# Crawler_Sensor_V2_0.net
KiCad netlist of a schematic drawn in Altium Designer
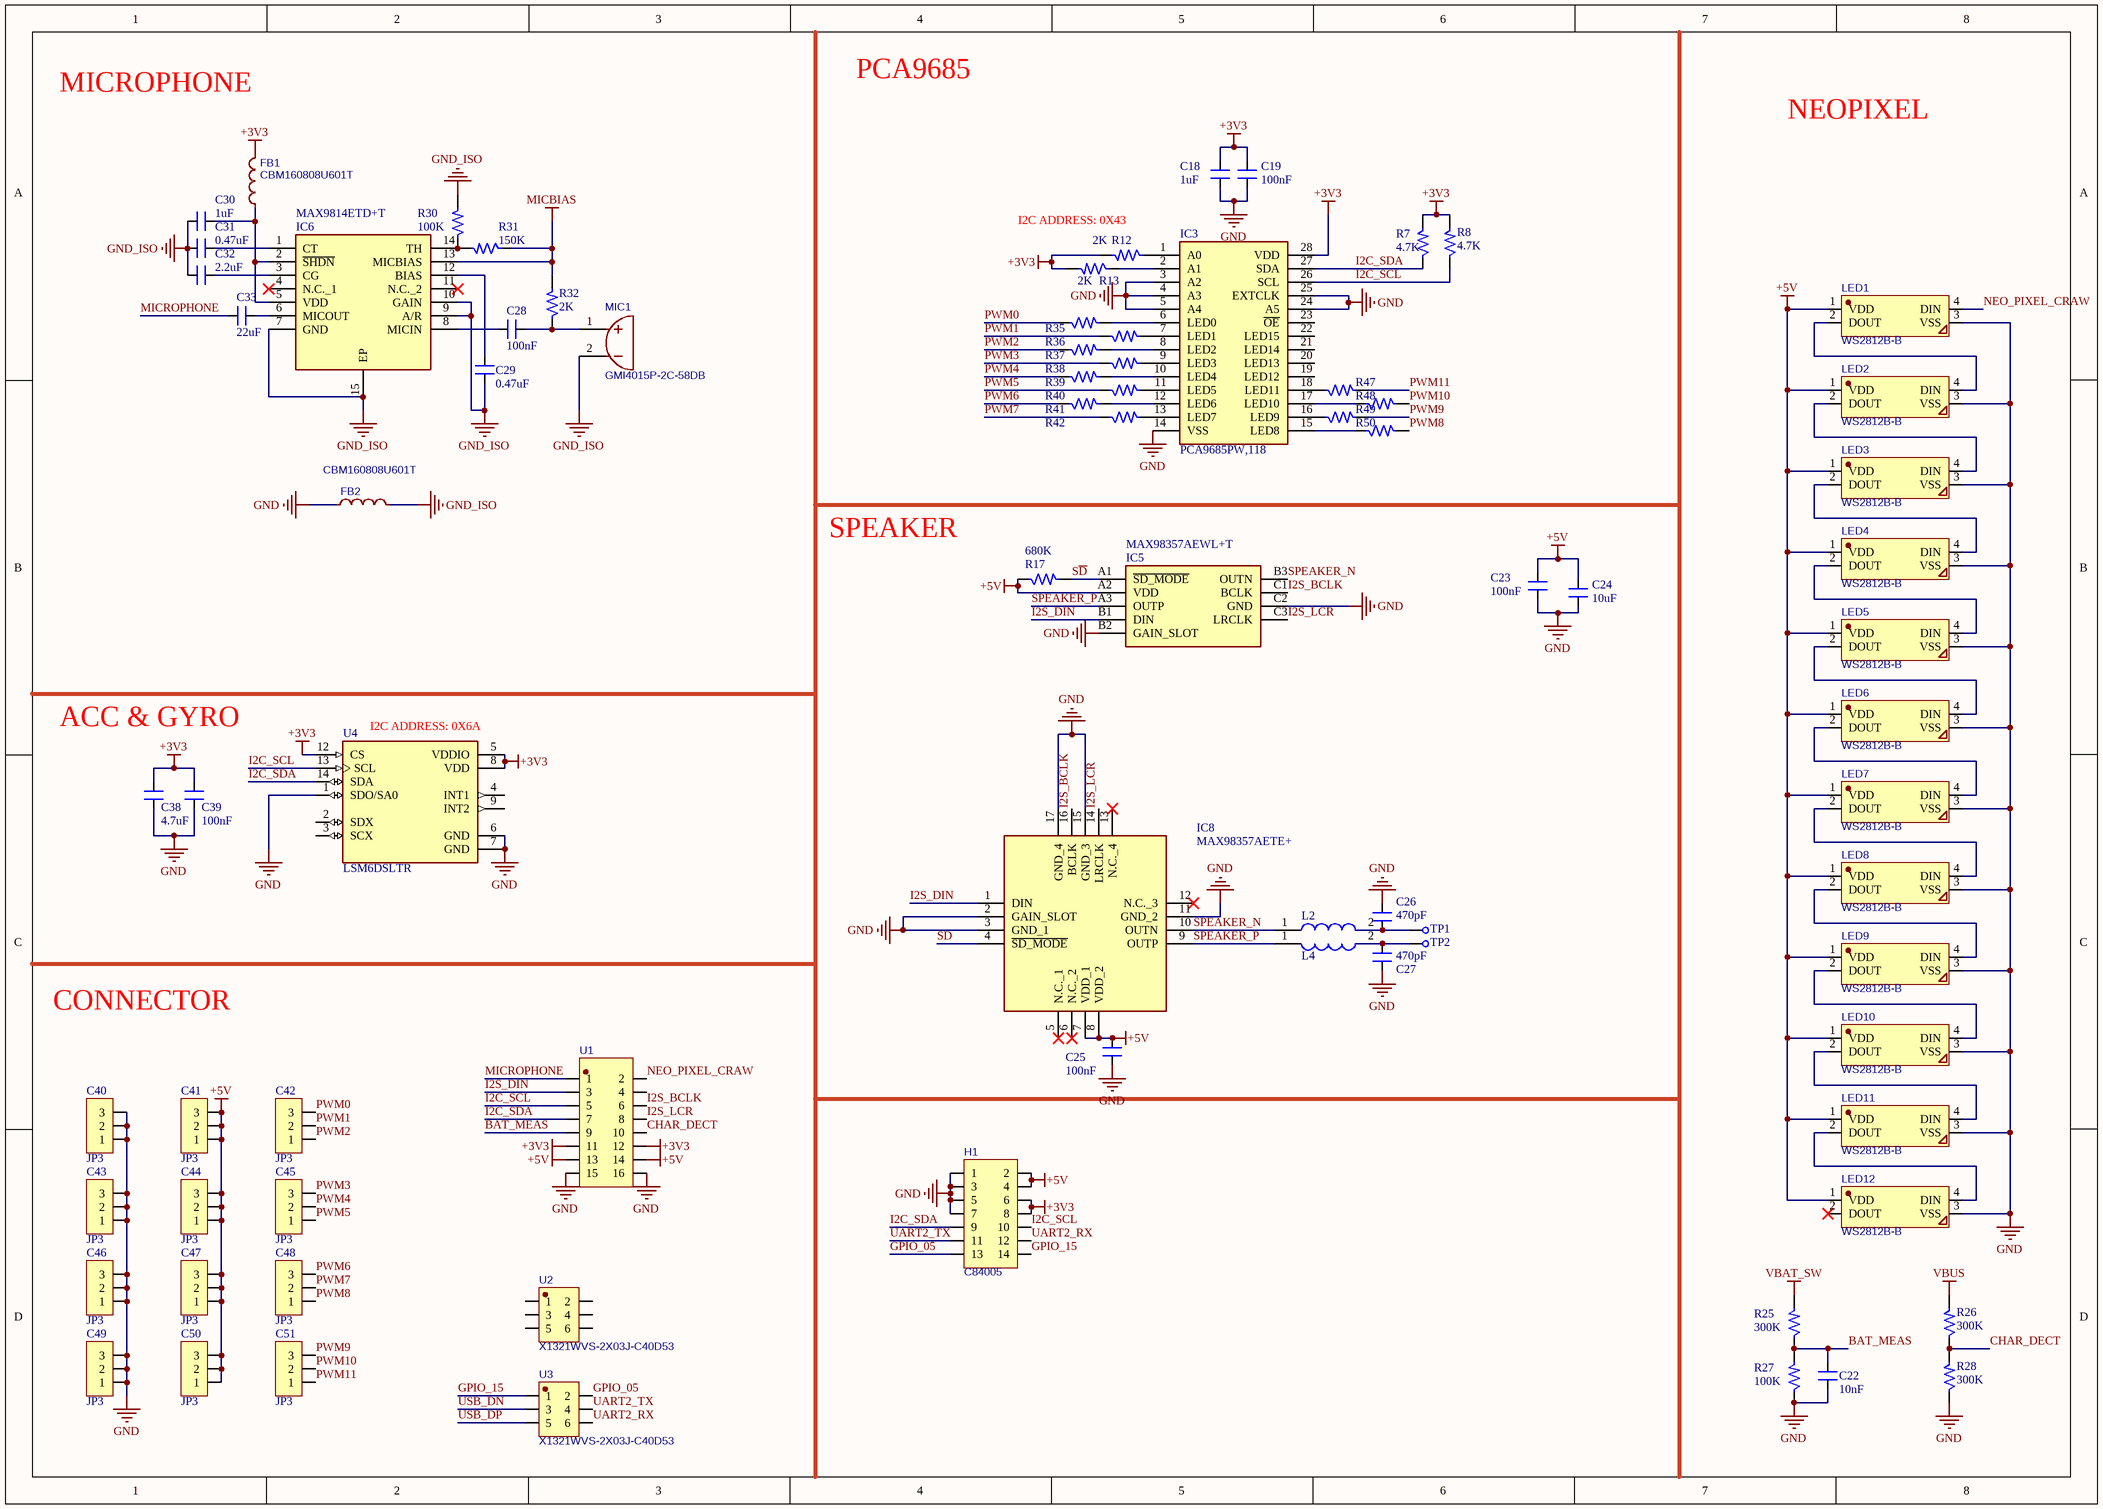
[diagram p0: Crawler_Sensor_V2.0.SchDoc]

(export (version "E")
  (design (tool "Eeschema 10.0.6"))
  (components
    (comp (ref "C18")
      (value "1uF")
      (footprint "CAP_0402")
      (description "1µF ±10% 16V Ceramic Capacitor X5R 0402 (1005 Metric)")
      (fields
        (field (name "MANUFACTURER") "Knowles Novacap")
        (field (name "MANUFACTURER PART NUMBER") "0402BW105K160YT")
      )
      (libsource (lib "EsteemPCB_SOM_Course_schlib") (part "CAP_1uF-16V-10%-0402"))
    )
    (comp (ref "C19")
      (value "100nF")
      (footprint "CAP_0402")
      (description "0.1µF ±10% 25V Ceramic Capacitor X7R 0402 (1005 Metric)")
      (fields
        (field (name "MANUFACTURER") "Walsin Technology Corporation")
        (field (name "MANUFACTURER PART NUMBER") "0402B104K250CT")
      )
      (libsource (lib "EsteemPCB_SOM_Course_schlib") (part "CAP_100nF-25V-10%-0402"))
    )
    (comp (ref "C22")
      (value "10nF")
      (footprint "CAP_0402")
      (description "10000pF ±10% 10V Ceramic Capacitor X7R 0402 (1005 Metric)")
      (fields
        (field (name "MANUFACTURER") "AVX Corporation")
        (field (name "MANUFACTURER PART NUMBER") "0402ZC103KAT2A")
      )
      (libsource (lib "EsteemPCB_SOM_Course_schlib") (part "CAP_10nF-10V-10%-0402"))
    )
    (comp (ref "C23")
      (value "100nF")
      (footprint "CAP_0402")
      (description "0.1µF ±10% 10V Ceramic Capacitor X7R 0402 (1005 Metric)")
      (fields
        (field (name "MANUFACTURER") "Yageo")
        (field (name "MANUFACTURER PART NUMBER") "CC0402KRX7R6BB104")
      )
      (libsource (lib "EsteemPCB_SOM_Course_schlib") (part "CAP_100nF-10V-10%-0402"))
    )
    (comp (ref "C24")
      (value "10uF")
      (footprint "CAP_0402")
      (description "10µF ±20% 10V Ceramic Capacitor X5R 0402 (1005 Metric)")
      (fields
        (field (name "MANUFACTURER PART NUMBER") "CL05A106MP5NUNC")
        (field (name "MANUFACTURER") "Samsung Electro-Mechanics")
      )
      (libsource (lib "EsteemPCB_SOM_Course_schlib") (part "CAP_10uF-10V-20%-0402"))
    )
    (comp (ref "C25")
      (value "100nF")
      (footprint "CAP_0402")
      (description "0.1µF ±10% 10V Ceramic Capacitor X7R 0402 (1005 Metric)")
      (fields
        (field (name "MANUFACTURER") "Yageo")
        (field (name "MANUFACTURER PART NUMBER") "CC0402KRX7R6BB104")
      )
      (libsource (lib "EsteemPCB_SOM_Course_schlib") (part "CAP_100nF-10V-10%-0402"))
    )
    (comp (ref "C26")
      (value "470pF")
      (footprint "CAP_0402")
      (description "470pF ±10% 10V Ceramic Capacitor C0G, NP0 0402 (1005 Metric)")
      (fields
        (field (name "MANUFACTURER") "KEMET")
        (field (name "MANUFACTURER PART NUMBER") "C0402C470K8GAC7867")
      )
      (libsource (lib "EsteemPCB_SOM_Course_schlib") (part "CAP_47pF-10V-10%-0402"))
    )
    (comp (ref "C27")
      (value "470pF")
      (footprint "CAP_0402")
      (description "470pF ±10% 10V Ceramic Capacitor C0G, NP0 0402 (1005 Metric)")
      (fields
        (field (name "MANUFACTURER") "KEMET")
        (field (name "MANUFACTURER PART NUMBER") "C0402C470K8GAC7867")
      )
      (libsource (lib "EsteemPCB_SOM_Course_schlib") (part "CAP_47pF-10V-10%-0402"))
    )
    (comp (ref "C28")
      (value "100nF")
      (footprint "CAP_0402")
      (description "0.1µF ±10% 10V Ceramic Capacitor X7R 0402 (1005 Metric)")
      (fields
        (field (name "MANUFACTURER") "Yageo")
        (field (name "MANUFACTURER PART NUMBER") "CC0402KRX7R6BB104")
      )
      (libsource (lib "EsteemPCB_SOM_Course_schlib") (part "CAP_100nF-10V-10%-0402"))
    )
    (comp (ref "C29")
      (value "0.47uF")
      (footprint "CAP_0402")
      (description "0.47µF ±10% 10V Ceramic Capacitor X6S 0402 (1005 Metric)")
      (fields
        (field (name "MANUFACTURER") "Murata Electronics")
        (field (name "MANUFACTURER PART NUMBER") "GRT155C81A105KE01D")
      )
      (libsource (lib "EsteemPCB_SOM_Course_schlib") (part "CAP_1uF-10V-10%-0402"))
    )
    (comp (ref "C30")
      (value "1uF")
      (footprint "CAP_0402")
      (description "1µF ±10% 10V Ceramic Capacitor X6S 0402 (1005 Metric)")
      (fields
        (field (name "MANUFACTURER") "Murata Electronics")
        (field (name "MANUFACTURER PART NUMBER") "GRT155C81A105KE01D")
      )
      (libsource (lib "EsteemPCB_SOM_Course_schlib") (part "CAP_1uF-10V-10%-0402"))
    )
    (comp (ref "C31")
      (value "0.47uF")
      (footprint "CAP_0402")
      (description "0.47µF ±10% 10V Ceramic Capacitor X6S 0402 (1005 Metric)")
      (fields
        (field (name "MANUFACTURER") "Murata Electronics")
        (field (name "MANUFACTURER PART NUMBER") "GRT155C81A105KE01D")
      )
      (libsource (lib "EsteemPCB_SOM_Course_schlib") (part "CAP_1uF-10V-10%-0402"))
    )
    (comp (ref "C32")
      (value "2.2uF")
      (footprint "CAP_0402")
      (description "2.2µF ±10% 10V Ceramic Capacitor X5R 0402 (1005 Metric)")
      (fields
        (field (name "MANUFACTURER") "Murata Electronics")
        (field (name "MANUFACTURER PART NUMBER") "GRM155R61A225KE95D")
      )
      (libsource (lib "EsteemPCB_SOM_Course_schlib") (part "CAP_2.2uF-10V-10%-0402"))
    )
    (comp (ref "C33")
      (value "22uF")
      (footprint "CAP_0603")
      (description "22µF ±20% 10V Ceramic Capacitor X5R 0603 (1608 Metric)")
      (fields
        (field (name "MANUFACTURER") "Murata Electronics")
        (field (name "MANUFACTURER PART NUMBER") "GRM188R61A226ME15D")
      )
      (libsource (lib "EsteemPCB_SOM_Course_schlib") (part "CAP_22uF-10V-20%-0603"))
    )
    (comp (ref "C38")
      (value "4.7uF")
      (footprint "CAP_0402")
      (description "4.7µF ±10% 10V Ceramic Capacitor X5R 0402 (1005 Metric)")
      (fields
        (field (name "MANUFACTURER") "Samsung Electro-Mechanics")
        (field (name "MANUFACTURER PART NUMBER") "CL05A475KP5NRNC")
      )
      (libsource (lib "EsteemPCB_SOM_Course_schlib") (part "CAP_4.7uF-10V-10%-0402"))
    )
    (comp (ref "C39")
      (value "100nF")
      (footprint "CAP_0402")
      (description "0.1µF ±10% 10V Ceramic Capacitor X7R 0402 (1005 Metric)")
      (fields
        (field (name "MANUFACTURER") "Yageo")
        (field (name "MANUFACTURER PART NUMBER") "CC0402KRX7R6BB104")
      )
      (libsource (lib "EsteemPCB_SOM_Course_schlib") (part "CAP_100nF-10V-10%-0402"))
    )
    (comp (ref "C40")
      (value "JP3")
      (footprint "JP3-D1T")
      (description "WR-PHD 2.54 mm Angled Socket Header")
      (fields
        (field (name "MANUFACTURER") "Würth Elektronik eiSos GmbH")
        (field (name "PARTNO") "613003143121")
        (field (name "CREATED BY") "Karrer Zheng")
      )
      (libsource (lib "LIBRARY") (part "JP3"))
    )
    (comp (ref "C41")
      (value "JP3")
      (footprint "JP3-D1T")
      (description "WR-PHD 2.54 mm Angled Socket Header")
      (fields
        (field (name "MANUFACTURER") "Würth Elektronik eiSos GmbH")
        (field (name "PARTNO") "613003143121")
        (field (name "CREATED BY") "Karrer Zheng")
      )
      (libsource (lib "LIBRARY") (part "JP3"))
    )
    (comp (ref "C42")
      (value "JP3")
      (footprint "JP3-D1T")
      (description "WR-PHD 2.54 mm Angled Socket Header")
      (fields
        (field (name "MANUFACTURER") "Würth Elektronik eiSos GmbH")
        (field (name "PARTNO") "613003143121")
        (field (name "CREATED BY") "Karrer Zheng")
      )
      (libsource (lib "LIBRARY") (part "JP3"))
    )
    (comp (ref "C43")
      (value "JP3")
      (footprint "JP3-D1T")
      (description "WR-PHD 2.54 mm Angled Socket Header")
      (fields
        (field (name "MANUFACTURER") "Würth Elektronik eiSos GmbH")
        (field (name "PARTNO") "613003143121")
        (field (name "CREATED BY") "Karrer Zheng")
      )
      (libsource (lib "LIBRARY") (part "JP3"))
    )
    (comp (ref "C44")
      (value "JP3")
      (footprint "JP3-D1T")
      (description "WR-PHD 2.54 mm Angled Socket Header")
      (fields
        (field (name "MANUFACTURER") "Würth Elektronik eiSos GmbH")
        (field (name "PARTNO") "613003143121")
        (field (name "CREATED BY") "Karrer Zheng")
      )
      (libsource (lib "LIBRARY") (part "JP3"))
    )
    (comp (ref "C45")
      (value "JP3")
      (footprint "JP3-D1T")
      (description "WR-PHD 2.54 mm Angled Socket Header")
      (fields
        (field (name "MANUFACTURER") "Würth Elektronik eiSos GmbH")
        (field (name "PARTNO") "613003143121")
        (field (name "CREATED BY") "Karrer Zheng")
      )
      (libsource (lib "LIBRARY") (part "JP3"))
    )
    (comp (ref "C46")
      (value "JP3")
      (footprint "JP3-D1T")
      (description "WR-PHD 2.54 mm Angled Socket Header")
      (fields
        (field (name "MANUFACTURER") "Würth Elektronik eiSos GmbH")
        (field (name "PARTNO") "613003143121")
        (field (name "CREATED BY") "Karrer Zheng")
      )
      (libsource (lib "LIBRARY") (part "JP3"))
    )
    (comp (ref "C47")
      (value "JP3")
      (footprint "JP3-D1T")
      (description "WR-PHD 2.54 mm Angled Socket Header")
      (fields
        (field (name "MANUFACTURER") "Würth Elektronik eiSos GmbH")
        (field (name "PARTNO") "613003143121")
        (field (name "CREATED BY") "Karrer Zheng")
      )
      (libsource (lib "LIBRARY") (part "JP3"))
    )
    (comp (ref "C48")
      (value "JP3")
      (footprint "JP3-D1T")
      (description "WR-PHD 2.54 mm Angled Socket Header")
      (fields
        (field (name "MANUFACTURER") "Würth Elektronik eiSos GmbH")
        (field (name "PARTNO") "613003143121")
        (field (name "CREATED BY") "Karrer Zheng")
      )
      (libsource (lib "LIBRARY") (part "JP3"))
    )
    (comp (ref "C49")
      (value "JP3")
      (footprint "JP3-D1T")
      (description "WR-PHD 2.54 mm Angled Socket Header")
      (fields
        (field (name "MANUFACTURER") "Würth Elektronik eiSos GmbH")
        (field (name "PARTNO") "613003143121")
        (field (name "CREATED BY") "Karrer Zheng")
      )
      (libsource (lib "LIBRARY") (part "JP3"))
    )
    (comp (ref "C50")
      (value "JP3")
      (footprint "JP3-D1T")
      (description "WR-PHD 2.54 mm Angled Socket Header")
      (fields
        (field (name "MANUFACTURER") "Würth Elektronik eiSos GmbH")
        (field (name "PARTNO") "613003143121")
        (field (name "CREATED BY") "Karrer Zheng")
      )
      (libsource (lib "LIBRARY") (part "JP3"))
    )
    (comp (ref "C51")
      (value "JP3")
      (footprint "JP3-D1T")
      (description "WR-PHD 2.54 mm Angled Socket Header")
      (fields
        (field (name "MANUFACTURER") "Würth Elektronik eiSos GmbH")
        (field (name "PARTNO") "613003143121")
        (field (name "CREATED BY") "Karrer Zheng")
      )
      (libsource (lib "LIBRARY") (part "JP3"))
    )
    (comp (ref "FB1")
      (value "CBM160808U601T")
      (footprint "L0603")
      (fields (field (name "BOM_SUPPLIER PART") "C394427") (field (name "CONTRIBUTOR") "LCSC"))
      (libsource (lib "") (part "CBM160808U601T_1"))
    )
    (comp (ref "FB2")
      (value "CBM160808U601T")
      (footprint "L0603")
      (fields (field (name "BOM_SUPPLIER PART") "C394427") (field (name "CONTRIBUTOR") "LCSC"))
      (libsource (lib "SamacSys") (part "CBM160808U601T"))
    )
    (comp (ref "H1")
      (value "C84005")
      (footprint "HDR-SMD_14P-P2.54-V-F-R2-C7-S2.54")
      (fields (field (name "BOM_MANUFACTURER PART") "2.54-2*7P立贴母") (field (name "CONTRIBUTOR") "LCSC"))
      (libsource (lib "SamacSys") (part "C84005"))
    )
    (comp (ref "IC3")
      (value "PCA9685PW,118")
      (footprint "SamacSys:SOP65P640X110-28N")
      (description "Integrated Circuit")
      (fields (field (name "MOUSER PART NUMBER") "771-PCA9685PW,118"))
      (libsource (lib "*") (part "PCA9685PW,118"))
    )
    (comp (ref "IC5")
      (value "MAX98357AEWL+T")
      (footprint "SamacSys:BGA9C40P3X3_144X135X69")
      (description "Integrated Circuit")
      (fields (field (name "MOUSER PART NUMBER") "700-MAX98357AEWL+T"))
      (libsource (lib "*") (part "MAX98357AEWL+T"))
    )
    (comp (ref "IC6")
      (value "MAX9814ETD+T")
      (footprint "SamacSys:SON40P300X300X80-15N")
      (description "Integrated Circuit")
      (fields (field (name "MOUSER PART NUMBER") "700-MAX9814ETDT"))
      (libsource (lib "*") (part "MAX9814ETD+T"))
    )
    (comp (ref "IC8")
      (value "MAX98357AETE+")
      (footprint "SamacSys:QFN50P300X300X80-17N")
      (description "Integrated Circuit")
      (fields (field (name "MOUSER PART NUMBER") "700-MAX98357AETE+"))
      (libsource (lib "SamacSys") (part "MAX98357AETE+"))
    )
    (comp (ref "L2")
      (value "MLF2012C680KT000")
      (footprint "INDC2012X145N")
      (description "Inductor")
      (fields (field (name "MOUSER PART NUMBER") "810-MLF2012C680KT000"))
      (libsource (lib "SamacSys") (part "MLF2012C680KT000"))
    )
    (comp (ref "L4")
      (value "MLF2012C680KT000")
      (footprint "INDC2012X145N")
      (description "Inductor")
      (fields (field (name "MOUSER PART NUMBER") "810-MLF2012C680KT000"))
      (libsource (lib "") (part "MLF2012C680KT000_1"))
    )
    (comp (ref "LED1")
      (value "WS2812B-B")
      (footprint "LED-SMD_4P-L5.0-W5.0-BL_TC5050RGB")
      (fields
        (field (name "BOM_MANUFACTURER PART") "WS2812B-B/W")
        (field (name "BOM_SUPPLIER PART") "C114586")
        (field (name "CONTRIBUTOR") "LCSC")
      )
      (libsource (lib "SamacSys") (part "WS2812B-B"))
    )
    (comp (ref "LED2")
      (value "WS2812B-B")
      (footprint "LED-SMD_4P-L5.0-W5.0-BL_TC5050RGB")
      (fields
        (field (name "BOM_MANUFACTURER PART") "WS2812B-B/W")
        (field (name "BOM_SUPPLIER PART") "C114586")
        (field (name "CONTRIBUTOR") "LCSC")
      )
      (libsource (lib "SamacSys") (part "WS2812B-B"))
    )
    (comp (ref "LED3")
      (value "WS2812B-B")
      (footprint "LED-SMD_4P-L5.0-W5.0-BL_TC5050RGB")
      (fields
        (field (name "BOM_MANUFACTURER PART") "WS2812B-B/W")
        (field (name "BOM_SUPPLIER PART") "C114586")
        (field (name "CONTRIBUTOR") "LCSC")
      )
      (libsource (lib "SamacSys") (part "WS2812B-B"))
    )
    (comp (ref "LED4")
      (value "WS2812B-B")
      (footprint "LED-SMD_4P-L5.0-W5.0-BL_TC5050RGB")
      (fields
        (field (name "BOM_MANUFACTURER PART") "WS2812B-B/W")
        (field (name "BOM_SUPPLIER PART") "C114586")
        (field (name "CONTRIBUTOR") "LCSC")
      )
      (libsource (lib "SamacSys") (part "WS2812B-B"))
    )
    (comp (ref "LED5")
      (value "WS2812B-B")
      (footprint "LED-SMD_4P-L5.0-W5.0-BL_TC5050RGB")
      (fields
        (field (name "BOM_MANUFACTURER PART") "WS2812B-B/W")
        (field (name "BOM_SUPPLIER PART") "C114586")
        (field (name "CONTRIBUTOR") "LCSC")
      )
      (libsource (lib "SamacSys") (part "WS2812B-B"))
    )
    (comp (ref "LED6")
      (value "WS2812B-B")
      (footprint "LED-SMD_4P-L5.0-W5.0-BL_TC5050RGB")
      (fields
        (field (name "BOM_MANUFACTURER PART") "WS2812B-B/W")
        (field (name "BOM_SUPPLIER PART") "C114586")
        (field (name "CONTRIBUTOR") "LCSC")
      )
      (libsource (lib "SamacSys") (part "WS2812B-B"))
    )
    (comp (ref "LED7")
      (value "WS2812B-B")
      (footprint "LED-SMD_4P-L5.0-W5.0-BL_TC5050RGB")
      (fields
        (field (name "BOM_MANUFACTURER PART") "WS2812B-B/W")
        (field (name "BOM_SUPPLIER PART") "C114586")
        (field (name "CONTRIBUTOR") "LCSC")
      )
      (libsource (lib "SamacSys") (part "WS2812B-B"))
    )
    (comp (ref "LED8")
      (value "WS2812B-B")
      (footprint "LED-SMD_4P-L5.0-W5.0-BL_TC5050RGB")
      (fields
        (field (name "BOM_MANUFACTURER PART") "WS2812B-B/W")
        (field (name "BOM_SUPPLIER PART") "C114586")
        (field (name "CONTRIBUTOR") "LCSC")
      )
      (libsource (lib "SamacSys") (part "WS2812B-B"))
    )
    (comp (ref "LED9")
      (value "WS2812B-B")
      (footprint "LED-SMD_4P-L5.0-W5.0-BL_TC5050RGB")
      (fields
        (field (name "BOM_MANUFACTURER PART") "WS2812B-B/W")
        (field (name "BOM_SUPPLIER PART") "C114586")
        (field (name "CONTRIBUTOR") "LCSC")
      )
      (libsource (lib "SamacSys") (part "WS2812B-B"))
    )
    (comp (ref "LED10")
      (value "WS2812B-B")
      (footprint "LED-SMD_4P-L5.0-W5.0-BL_TC5050RGB")
      (fields
        (field (name "BOM_MANUFACTURER PART") "WS2812B-B/W")
        (field (name "BOM_SUPPLIER PART") "C114586")
        (field (name "CONTRIBUTOR") "LCSC")
      )
      (libsource (lib "SamacSys") (part "WS2812B-B"))
    )
    (comp (ref "LED11")
      (value "WS2812B-B")
      (footprint "LED-SMD_4P-L5.0-W5.0-BL_TC5050RGB")
      (fields
        (field (name "BOM_MANUFACTURER PART") "WS2812B-B/W")
        (field (name "BOM_SUPPLIER PART") "C114586")
        (field (name "CONTRIBUTOR") "LCSC")
      )
      (libsource (lib "SamacSys") (part "WS2812B-B"))
    )
    (comp (ref "LED12")
      (value "WS2812B-B")
      (footprint "LED-SMD_4P-L5.0-W5.0-BL_TC5050RGB")
      (fields
        (field (name "BOM_MANUFACTURER PART") "WS2812B-B/W")
        (field (name "BOM_SUPPLIER PART") "C114586")
        (field (name "CONTRIBUTOR") "LCSC")
      )
      (libsource (lib "SamacSys") (part "WS2812B-B"))
    )
    (comp (ref "MIC1")
      (value "GMI4015P-2C-58DB")
      (footprint "MIC-TH_BD4.0-P1.40-D0.4-L-FD")
      (fields
        (field (name "BOM_SUPPLIER PART") "C233300")
        (field (name "BOM_MANUFACTURER PART") "GMI4015P-2C-58db")
        (field (name "CONTRIBUTOR") "LCSC")
      )
      (libsource (lib "SamacSys") (part "GMI4015P-2C-58DB"))
    )
    (comp (ref "R7")
      (value "4.7K")
      (footprint "RES_0402")
      (description "4.7 kOhms ±1% 0.1W, 1/10W Chip Resistor 0402 (1005 Metric) Automotive AEC-Q200 Thick Film")
      (fields
        (field (name "MANUFACTURER") "Panasonic Electronic Components")
        (field (name "MANUFACTURER PART NUMBER") "ERJ-2RKF4701X")
      )
      (libsource (lib "EsteemPCB_SOM_Course_schlib") (part "RES_4.7K-0.1W-1%-0402"))
    )
    (comp (ref "R8")
      (value "4.7K")
      (footprint "RES_0402")
      (description "4.7 kOhms ±1% 0.1W, 1/10W Chip Resistor 0402 (1005 Metric) Automotive AEC-Q200 Thick Film")
      (fields
        (field (name "MANUFACTURER") "Panasonic Electronic Components")
        (field (name "MANUFACTURER PART NUMBER") "ERJ-2RKF4701X")
      )
      (libsource (lib "EsteemPCB_SOM_Course_schlib") (part "RES_4.7K-0.1W-1%-0402"))
    )
    (comp (ref "R12")
      (value "2K")
      (footprint "RES_0402")
      (description "2 kOhms ±1% 0.1W, 1/10W Chip Resistor 0402 (1005 Metric) Automotive AEC-Q200 Thick Film")
      (fields
        (field (name "MANUFACTURER") "Panasonic Electronic Components")
        (field (name "MANUFACTURER PART NUMBER") "ERJ-2RKF2003X")
      )
      (libsource (lib "EsteemPCB_SOM_Course_schlib") (part "RES_200K-0.1W-1%-0402"))
    )
    (comp (ref "R13")
      (value "2K")
      (footprint "RES_0402")
      (description "2 kOhms ±1% 0.1W, 1/10W Chip Resistor 0402 (1005 Metric) Automotive AEC-Q200 Thick Film")
      (fields
        (field (name "MANUFACTURER") "Panasonic Electronic Components")
        (field (name "MANUFACTURER PART NUMBER") "ERJ-2RKF2003X")
      )
      (libsource (lib "EsteemPCB_SOM_Course_schlib") (part "RES_200K-0.1W-1%-0402"))
    )
    (comp (ref "R17")
      (value "680K")
      (footprint "RES_0402")
      (description "680 kOhms ±1% 0.1W, 1/10W Chip Resistor 0402 (1005 Metric) Anti-Sulfur Thin Film")
      (fields
        (field (name "MANUFACTURER") "Vishay Beyschlag/Draloric/BC Components")
        (field (name "MANUFACTURER PART NUMBER") "MCS04020C6801FE000")
      )
      (libsource (lib "EsteemPCB_SOM_Course_schlib") (part "RES_6.8K-0.1W-1%-0402"))
    )
    (comp (ref "R25")
      (value "300K")
      (footprint "RES_0402")
      (description "300 kOhms ±1% 0.1W, 1/10W Chip Resistor 0402 (1005 Metric) Anti-Sulfur Thin Film")
      (fields
        (field (name "MANUFACTURER") "Vishay Beyschlag/Draloric/BC Components")
        (field (name "MANUFACTURER PART NUMBER") "MCS04020C1003FE000")
      )
      (libsource (lib "EsteemPCB_SOM_Course_schlib") (part "RES_100K-0.1W-1%-0402"))
    )
    (comp (ref "R26")
      (value "300K")
      (footprint "RES_0402")
      (description "300 kOhms ±1% 0.1W, 1/10W Chip Resistor 0402 (1005 Metric) Anti-Sulfur Thin Film")
      (fields
        (field (name "MANUFACTURER") "Vishay Beyschlag/Draloric/BC Components")
        (field (name "MANUFACTURER PART NUMBER") "MCS04020C1003FE000")
      )
      (libsource (lib "EsteemPCB_SOM_Course_schlib") (part "RES_100K-0.1W-1%-0402"))
    )
    (comp (ref "R27")
      (value "100K")
      (footprint "RES_0402")
      (description "100 kOhms ±1% 0.1W, 1/10W Chip Resistor 0402 (1005 Metric) Anti-Sulfur Thin Film")
      (fields
        (field (name "MANUFACTURER") "Vishay Beyschlag/Draloric/BC Components")
        (field (name "MANUFACTURER PART NUMBER") "MCS04020C1003FE000")
      )
      (libsource (lib "EsteemPCB_SOM_Course_schlib") (part "RES_100K-0.1W-1%-0402"))
    )
    (comp (ref "R28")
      (value "300K")
      (footprint "RES_0402")
      (description "300 kOhms ±1% 0.1W, 1/10W Chip Resistor 0402 (1005 Metric) Anti-Sulfur Thin Film")
      (fields
        (field (name "MANUFACTURER") "Vishay Beyschlag/Draloric/BC Components")
        (field (name "MANUFACTURER PART NUMBER") "MCS04020C1003FE000")
      )
      (libsource (lib "EsteemPCB_SOM_Course_schlib") (part "RES_100K-0.1W-1%-0402"))
    )
    (comp (ref "R30")
      (value "100K")
      (footprint "RES_0402")
      (description "100 kOhms ±1% 0.1W, 1/10W Chip Resistor 0402 (1005 Metric) Anti-Sulfur Thin Film")
      (fields
        (field (name "MANUFACTURER") "Vishay Beyschlag/Draloric/BC Components")
        (field (name "MANUFACTURER PART NUMBER") "MCS04020C1003FE000")
      )
      (libsource (lib "EsteemPCB_SOM_Course_schlib") (part "RES_100K-0.1W-1%-0402"))
    )
    (comp (ref "R31")
      (value "150K")
      (footprint "RES_0402")
      (description "150 kOhms ±1% 0.1W, 1/10W Chip Resistor 0402 (1005 Metric) Anti-Sulfur Thin Film")
      (fields
        (field (name "MANUFACTURER") "Vishay Beyschlag/Draloric/BC Components")
        (field (name "MANUFACTURER PART NUMBER") "MCS04020C1003FE000")
      )
      (libsource (lib "EsteemPCB_SOM_Course_schlib") (part "RES_100K-0.1W-1%-0402"))
    )
    (comp (ref "R32")
      (value "2K")
      (footprint "RES_0402")
      (description "2 kOhms ±1% 0.1W, 1/10W Chip Resistor 0402 (1005 Metric) Automotive AEC-Q200 Thick Film")
      (fields
        (field (name "MANUFACTURER") "Panasonic Electronic Components")
        (field (name "MANUFACTURER PART NUMBER") "ERJ-2RKF2003X")
      )
      (libsource (lib "EsteemPCB_SOM_Course_schlib") (part "RES_200K-0.1W-1%-0402"))
    )
    (comp (ref "R35")
      (value "220R")
      (footprint "RES_0402")
      (description "220 Ohms ±1% 0.1W, 1/10W Chip Resistor 0402 (1005 Metric) Automotive AEC-Q200 Thick Film")
      (fields
        (field (name "MANUFACTURER") "Panasonic Electronic Components")
        (field (name "MANUFACTURER PART NUMBER") "ERJ-2RKF2400X")
      )
      (libsource (lib "EsteemPCB_SOM_Course_schlib") (part "RES_240R-0.1W-1%-0402"))
    )
    (comp (ref "R36")
      (value "220R")
      (footprint "RES_0402")
      (description "220 Ohms ±1% 0.1W, 1/10W Chip Resistor 0402 (1005 Metric) Automotive AEC-Q200 Thick Film")
      (fields
        (field (name "MANUFACTURER") "Panasonic Electronic Components")
        (field (name "MANUFACTURER PART NUMBER") "ERJ-2RKF2400X")
      )
      (libsource (lib "EsteemPCB_SOM_Course_schlib") (part "RES_240R-0.1W-1%-0402"))
    )
    (comp (ref "R37")
      (value "220R")
      (footprint "RES_0402")
      (description "220 Ohms ±1% 0.1W, 1/10W Chip Resistor 0402 (1005 Metric) Automotive AEC-Q200 Thick Film")
      (fields
        (field (name "MANUFACTURER") "Panasonic Electronic Components")
        (field (name "MANUFACTURER PART NUMBER") "ERJ-2RKF2400X")
      )
      (libsource (lib "EsteemPCB_SOM_Course_schlib") (part "RES_240R-0.1W-1%-0402"))
    )
    (comp (ref "R38")
      (value "220R")
      (footprint "RES_0402")
      (description "220 Ohms ±1% 0.1W, 1/10W Chip Resistor 0402 (1005 Metric) Automotive AEC-Q200 Thick Film")
      (fields
        (field (name "MANUFACTURER") "Panasonic Electronic Components")
        (field (name "MANUFACTURER PART NUMBER") "ERJ-2RKF2400X")
      )
      (libsource (lib "EsteemPCB_SOM_Course_schlib") (part "RES_240R-0.1W-1%-0402"))
    )
    (comp (ref "R39")
      (value "220R")
      (footprint "RES_0402")
      (description "220 Ohms ±1% 0.1W, 1/10W Chip Resistor 0402 (1005 Metric) Automotive AEC-Q200 Thick Film")
      (fields
        (field (name "MANUFACTURER") "Panasonic Electronic Components")
        (field (name "MANUFACTURER PART NUMBER") "ERJ-2RKF2400X")
      )
      (libsource (lib "EsteemPCB_SOM_Course_schlib") (part "RES_240R-0.1W-1%-0402"))
    )
    (comp (ref "R40")
      (value "220R")
      (footprint "RES_0402")
      (description "220 Ohms ±1% 0.1W, 1/10W Chip Resistor 0402 (1005 Metric) Automotive AEC-Q200 Thick Film")
      (fields
        (field (name "MANUFACTURER") "Panasonic Electronic Components")
        (field (name "MANUFACTURER PART NUMBER") "ERJ-2RKF2400X")
      )
      (libsource (lib "EsteemPCB_SOM_Course_schlib") (part "RES_240R-0.1W-1%-0402"))
    )
    (comp (ref "R41")
      (value "220R")
      (footprint "RES_0402")
      (description "220 Ohms ±1% 0.1W, 1/10W Chip Resistor 0402 (1005 Metric) Automotive AEC-Q200 Thick Film")
      (fields
        (field (name "MANUFACTURER") "Panasonic Electronic Components")
        (field (name "MANUFACTURER PART NUMBER") "ERJ-2RKF2400X")
      )
      (libsource (lib "EsteemPCB_SOM_Course_schlib") (part "RES_240R-0.1W-1%-0402"))
    )
    (comp (ref "R42")
      (value "220R")
      (footprint "RES_0402")
      (description "220 Ohms ±1% 0.1W, 1/10W Chip Resistor 0402 (1005 Metric) Automotive AEC-Q200 Thick Film")
      (fields
        (field (name "MANUFACTURER") "Panasonic Electronic Components")
        (field (name "MANUFACTURER PART NUMBER") "ERJ-2RKF2400X")
      )
      (libsource (lib "EsteemPCB_SOM_Course_schlib") (part "RES_240R-0.1W-1%-0402"))
    )
    (comp (ref "R47")
      (value "220R")
      (footprint "RES_0402")
      (description "220 Ohms ±1% 0.1W, 1/10W Chip Resistor 0402 (1005 Metric) Automotive AEC-Q200 Thick Film")
      (fields
        (field (name "MANUFACTURER") "Panasonic Electronic Components")
        (field (name "MANUFACTURER PART NUMBER") "ERJ-2RKF2400X")
      )
      (libsource (lib "EsteemPCB_SOM_Course_schlib") (part "RES_240R-0.1W-1%-0402"))
    )
    (comp (ref "R48")
      (value "220R")
      (footprint "RES_0402")
      (description "220 Ohms ±1% 0.1W, 1/10W Chip Resistor 0402 (1005 Metric) Automotive AEC-Q200 Thick Film")
      (fields
        (field (name "MANUFACTURER") "Panasonic Electronic Components")
        (field (name "MANUFACTURER PART NUMBER") "ERJ-2RKF2400X")
      )
      (libsource (lib "EsteemPCB_SOM_Course_schlib") (part "RES_240R-0.1W-1%-0402"))
    )
    (comp (ref "R49")
      (value "220R")
      (footprint "RES_0402")
      (description "220 Ohms ±1% 0.1W, 1/10W Chip Resistor 0402 (1005 Metric) Automotive AEC-Q200 Thick Film")
      (fields
        (field (name "MANUFACTURER") "Panasonic Electronic Components")
        (field (name "MANUFACTURER PART NUMBER") "ERJ-2RKF2400X")
      )
      (libsource (lib "EsteemPCB_SOM_Course_schlib") (part "RES_240R-0.1W-1%-0402"))
    )
    (comp (ref "R50")
      (value "220R")
      (footprint "RES_0402")
      (description "220 Ohms ±1% 0.1W, 1/10W Chip Resistor 0402 (1005 Metric) Automotive AEC-Q200 Thick Film")
      (fields
        (field (name "MANUFACTURER") "Panasonic Electronic Components")
        (field (name "MANUFACTURER PART NUMBER") "ERJ-2RKF2400X")
      )
      (libsource (lib "EsteemPCB_SOM_Course_schlib") (part "RES_240R-0.1W-1%-0402"))
    )
    (comp (ref "TP1")
      (value "TEST POINT")
      (footprint "TEST POINT_30")
      (description "0.4mm hole size Test point")
      (fields (field (name "MANUFACTURER PART NUMBER") "NA"))
      (libsource (lib "EsteemPCB_SOM_Course_schlib") (part "TEST POINT"))
    )
    (comp (ref "TP2")
      (value "TEST POINT")
      (footprint "TEST POINT_30")
      (description "0.4mm hole size Test point")
      (fields (field (name "MANUFACTURER PART NUMBER") "NA"))
      (libsource (lib "EsteemPCB_SOM_Course_schlib") (part "TEST POINT"))
    )
    (comp (ref "U1")
      (value "X1321WVS-2X08J-C40D53")
      (footprint "HDR-SMD_16P-P1.27-V-M-R2-C8-LS5.3")
      (fields
        (field (name "BOM_SUPPLIER PART") "C2881913")
        (field (name "BOM_MANUFACTURER PART") "X1321WVS-2x08J-C40D53")
        (field (name "CONTRIBUTOR") "LCSC")
      )
      (libsource (lib "SamacSys") (part "X1321WVS-2X08J-C40D53"))
    )
    (comp (ref "U2")
      (value "X1321WVS-2X03J-C40D53")
      (footprint "HDR-SMD_6P-P1.27-V-M-R2-C3-LS5.3")
      (fields
        (field (name "BOM_SUPPLIER PART") "C2881908")
        (field (name "BOM_MANUFACTURER PART") "X1321WVS-2x03J-C40D53")
        (field (name "CONTRIBUTOR") "LCSC")
      )
      (libsource (lib "SamacSys") (part "X1321WVS-2X03J-C40D53"))
    )
    (comp (ref "U3")
      (value "X1321WVS-2X03J-C40D53")
      (footprint "HDR-SMD_6P-P1.27-V-M-R2-C3-LS5.3")
      (fields
        (field (name "BOM_SUPPLIER PART") "C2881908")
        (field (name "BOM_MANUFACTURER PART") "X1321WVS-2x03J-C40D53")
        (field (name "CONTRIBUTOR") "LCSC")
      )
      (libsource (lib "SamacSys") (part "X1321WVS-2X03J-C40D53"))
    )
    (comp (ref "U4")
      (value "LSM6DSLTR")
      (footprint "PQFN50P300X250X86-14N")
      (description "Accelerometer, Gyroscope, Temperature, 6 Axis Sensor IÂ²C, SPI Output")
      (fields (field (name "MF") "STMicroelectronics"))
      (libsource (lib "SamacSys") (part "LSM6DSLTR"))
    )
  )
  (nets
    (net (code "1") (name "+3V3") (class "Default")
      (node (ref "C18") (pin "2") (pinfunction "2_2") (pintype "passive"))
      (node (ref "C19") (pin "2") (pinfunction "2_2") (pintype "passive"))
      (node (ref "C38") (pin "2") (pinfunction "2_2") (pintype "passive"))
      (node (ref "C39") (pin "2") (pinfunction "2_2") (pintype "passive"))
      (node (ref "FB1") (pin "2") (pinfunction "2_2") (pintype "passive"))
      (node (ref "H1") (pin "6") (pinfunction "6_6") (pintype "passive"))
      (node (ref "H1") (pin "8") (pinfunction "8_8") (pintype "passive"))
      (node (ref "IC3") (pin "28") (pinfunction "VDD_28") (pintype "passive"))
      (node (ref "R12") (pin "2") (pinfunction "2_2") (pintype "passive"))
      (node (ref "R13") (pin "2") (pinfunction "2_2") (pintype "passive"))
      (node (ref "R7") (pin "2") (pinfunction "2_2") (pintype "passive"))
      (node (ref "R8") (pin "2") (pinfunction "2_2") (pintype "passive"))
      (node (ref "U1") (pin "11") (pinfunction "11_11") (pintype "passive"))
      (node (ref "U1") (pin "12") (pinfunction "12_12") (pintype "passive"))
      (node (ref "U4") (pin "12") (pinfunction "CS_12") (pintype "input"))
      (node (ref "U4") (pin "5") (pinfunction "VDDIO_5") (pintype "power_in"))
      (node (ref "U4") (pin "8") (pinfunction "VDD_8") (pintype "power_in"))
    )
    (net (code "2") (name "+5V") (class "Default")
      (node (ref "C23") (pin "2") (pinfunction "2_2") (pintype "passive"))
      (node (ref "C24") (pin "2") (pinfunction "2_2") (pintype "passive"))
      (node (ref "C25") (pin "2") (pinfunction "2_2") (pintype "passive"))
      (node (ref "C41") (pin "1") (pinfunction "1_1") (pintype "passive"))
      (node (ref "C41") (pin "2") (pinfunction "2_2") (pintype "passive"))
      (node (ref "C41") (pin "3") (pinfunction "3_3") (pintype "passive"))
      (node (ref "C44") (pin "1") (pinfunction "1_1") (pintype "passive"))
      (node (ref "C44") (pin "2") (pinfunction "2_2") (pintype "passive"))
      (node (ref "C44") (pin "3") (pinfunction "3_3") (pintype "passive"))
      (node (ref "C47") (pin "1") (pinfunction "1_1") (pintype "passive"))
      (node (ref "C47") (pin "2") (pinfunction "2_2") (pintype "passive"))
      (node (ref "C47") (pin "3") (pinfunction "3_3") (pintype "passive"))
      (node (ref "C50") (pin "1") (pinfunction "1_1") (pintype "passive"))
      (node (ref "C50") (pin "2") (pinfunction "2_2") (pintype "passive"))
      (node (ref "C50") (pin "3") (pinfunction "3_3") (pintype "passive"))
      (node (ref "H1") (pin "2") (pinfunction "2_2") (pintype "passive"))
      (node (ref "H1") (pin "4") (pinfunction "4_4") (pintype "passive"))
      (node (ref "IC5") (pin "A2") (pinfunction "VDD_A2") (pintype "passive"))
      (node (ref "IC8") (pin "7") (pinfunction "VDD_1_7") (pintype "passive"))
      (node (ref "IC8") (pin "8") (pinfunction "VDD_2_8") (pintype "passive"))
      (node (ref "LED1") (pin "1") (pinfunction "VDD_1") (pintype "passive"))
      (node (ref "LED10") (pin "1") (pinfunction "VDD_1") (pintype "passive"))
      (node (ref "LED11") (pin "1") (pinfunction "VDD_1") (pintype "passive"))
      (node (ref "LED12") (pin "1") (pinfunction "VDD_1") (pintype "passive"))
      (node (ref "LED2") (pin "1") (pinfunction "VDD_1") (pintype "passive"))
      (node (ref "LED3") (pin "1") (pinfunction "VDD_1") (pintype "passive"))
      (node (ref "LED4") (pin "1") (pinfunction "VDD_1") (pintype "passive"))
      (node (ref "LED5") (pin "1") (pinfunction "VDD_1") (pintype "passive"))
      (node (ref "LED6") (pin "1") (pinfunction "VDD_1") (pintype "passive"))
      (node (ref "LED7") (pin "1") (pinfunction "VDD_1") (pintype "passive"))
      (node (ref "LED8") (pin "1") (pinfunction "VDD_1") (pintype "passive"))
      (node (ref "LED9") (pin "1") (pinfunction "VDD_1") (pintype "passive"))
      (node (ref "R17") (pin "1") (pinfunction "1_1") (pintype "passive"))
      (node (ref "U1") (pin "13") (pinfunction "13_13") (pintype "passive"))
      (node (ref "U1") (pin "14") (pinfunction "14_14") (pintype "passive"))
    )
    (net (code "3") (name "/BAT_MEAS") (class "Default")
      (node (ref "C22") (pin "2") (pinfunction "2_2") (pintype "passive"))
      (node (ref "R25") (pin "1") (pinfunction "1_1") (pintype "passive"))
      (node (ref "R27") (pin "2") (pinfunction "2_2") (pintype "passive"))
      (node (ref "U1") (pin "9") (pinfunction "9_9") (pintype "passive"))
    )
    (net (code "4") (name "/CHAR_DECT") (class "Default")
      (node (ref "R26") (pin "1") (pinfunction "1_1") (pintype "passive"))
      (node (ref "R28") (pin "2") (pinfunction "2_2") (pintype "passive"))
      (node (ref "U1") (pin "10") (pinfunction "10_10") (pintype "passive"))
    )
    (net (code "5") (name "/GPIO_05") (class "Default")
      (node (ref "H1") (pin "13") (pinfunction "13_13") (pintype "passive"))
      (node (ref "U3") (pin "2") (pinfunction "2_2") (pintype "passive"))
    )
    (net (code "6") (name "/GPIO_15") (class "Default")
      (node (ref "H1") (pin "14") (pinfunction "14_14") (pintype "passive"))
      (node (ref "U3") (pin "1") (pinfunction "1_1") (pintype "passive"))
    )
    (net (code "7") (name "/I2C_SCL") (class "Default")
      (node (ref "H1") (pin "10") (pinfunction "10_10") (pintype "passive"))
      (node (ref "IC3") (pin "26") (pinfunction "SCL_26") (pintype "passive"))
      (node (ref "R8") (pin "1") (pinfunction "1_1") (pintype "passive"))
      (node (ref "U1") (pin "5") (pinfunction "5_5") (pintype "passive"))
      (node (ref "U4") (pin "13") (pinfunction "SCL_13") (pintype "input"))
    )
    (net (code "8") (name "/I2C_SDA") (class "Default")
      (node (ref "H1") (pin "9") (pinfunction "9_9") (pintype "passive"))
      (node (ref "IC3") (pin "27") (pinfunction "SDA_27") (pintype "passive"))
      (node (ref "R7") (pin "1") (pinfunction "1_1") (pintype "passive"))
      (node (ref "U1") (pin "7") (pinfunction "7_7") (pintype "passive"))
      (node (ref "U4") (pin "14") (pinfunction "SDA_14") (pintype "bidirectional"))
    )
    (net (code "9") (name "/I2S_BCLK") (class "Default")
      (node (ref "IC5") (pin "C1") (pinfunction "BCLK_C1") (pintype "passive"))
      (node (ref "IC8") (pin "16") (pinfunction "BCLK_16") (pintype "passive"))
      (node (ref "U1") (pin "6") (pinfunction "6_6") (pintype "passive"))
    )
    (net (code "10") (name "/I2S_DIN") (class "Default")
      (node (ref "IC5") (pin "B1") (pinfunction "DIN_B1") (pintype "passive"))
      (node (ref "IC8") (pin "1") (pinfunction "DIN_1") (pintype "passive"))
      (node (ref "U1") (pin "3") (pinfunction "3_3") (pintype "passive"))
    )
    (net (code "11") (name "/I2S_LCR") (class "Default")
      (node (ref "IC5") (pin "C3") (pinfunction "LRCLK_C3") (pintype "passive"))
      (node (ref "IC8") (pin "14") (pinfunction "LRCLK_14") (pintype "passive"))
      (node (ref "U1") (pin "8") (pinfunction "8_8") (pintype "passive"))
    )
    (net (code "12") (name "/MICROPHONE") (class "Default")
      (node (ref "C33") (pin "1") (pinfunction "1_1") (pintype "passive"))
      (node (ref "U1") (pin "1") (pinfunction "1_1") (pintype "passive"))
    )
    (net (code "13") (name "/NEO_PIXEL_CRAW") (class "Default")
      (node (ref "LED1") (pin "4") (pinfunction "DIN_4") (pintype "passive"))
      (node (ref "U1") (pin "2") (pinfunction "2_2") (pintype "passive"))
    )
    (net (code "14") (name "/PWM0") (class "Default")
      (node (ref "C42") (pin "3") (pinfunction "3_3") (pintype "passive"))
      (node (ref "R35") (pin "1") (pinfunction "1_1") (pintype "passive"))
    )
    (net (code "15") (name "/PWM1") (class "Default")
      (node (ref "C42") (pin "2") (pinfunction "2_2") (pintype "passive"))
      (node (ref "R36") (pin "1") (pinfunction "1_1") (pintype "passive"))
    )
    (net (code "16") (name "/PWM2") (class "Default")
      (node (ref "C42") (pin "1") (pinfunction "1_1") (pintype "passive"))
      (node (ref "R37") (pin "1") (pinfunction "1_1") (pintype "passive"))
    )
    (net (code "17") (name "/PWM3") (class "Default")
      (node (ref "C45") (pin "3") (pinfunction "3_3") (pintype "passive"))
      (node (ref "R38") (pin "1") (pinfunction "1_1") (pintype "passive"))
    )
    (net (code "18") (name "/PWM4") (class "Default")
      (node (ref "C45") (pin "2") (pinfunction "2_2") (pintype "passive"))
      (node (ref "R39") (pin "1") (pinfunction "1_1") (pintype "passive"))
    )
    (net (code "19") (name "/PWM5") (class "Default")
      (node (ref "C45") (pin "1") (pinfunction "1_1") (pintype "passive"))
      (node (ref "R40") (pin "1") (pinfunction "1_1") (pintype "passive"))
    )
    (net (code "20") (name "/PWM6") (class "Default")
      (node (ref "C48") (pin "3") (pinfunction "3_3") (pintype "passive"))
      (node (ref "R41") (pin "1") (pinfunction "1_1") (pintype "passive"))
    )
    (net (code "21") (name "/PWM7") (class "Default")
      (node (ref "C48") (pin "2") (pinfunction "2_2") (pintype "passive"))
      (node (ref "R42") (pin "1") (pinfunction "1_1") (pintype "passive"))
    )
    (net (code "22") (name "/PWM8") (class "Default")
      (node (ref "C48") (pin "1") (pinfunction "1_1") (pintype "passive"))
      (node (ref "R50") (pin "2") (pinfunction "2_2") (pintype "passive"))
    )
    (net (code "23") (name "/PWM9") (class "Default")
      (node (ref "C51") (pin "3") (pinfunction "3_3") (pintype "passive"))
      (node (ref "R49") (pin "2") (pinfunction "2_2") (pintype "passive"))
    )
    (net (code "24") (name "/PWM10") (class "Default")
      (node (ref "C51") (pin "2") (pinfunction "2_2") (pintype "passive"))
      (node (ref "R48") (pin "2") (pinfunction "2_2") (pintype "passive"))
    )
    (net (code "25") (name "/PWM11") (class "Default")
      (node (ref "C51") (pin "1") (pinfunction "1_1") (pintype "passive"))
      (node (ref "R47") (pin "2") (pinfunction "2_2") (pintype "passive"))
    )
    (net (code "26") (name "/SPEAKER_N") (class "Default")
      (node (ref "IC5") (pin "B3") (pinfunction "OUTN_B3") (pintype "passive"))
      (node (ref "IC8") (pin "10") (pinfunction "OUTN_10") (pintype "passive"))
      (node (ref "L2") (pin "1") (pinfunction "1_1") (pintype "passive"))
    )
    (net (code "27") (name "/SPEAKER_P") (class "Default")
      (node (ref "IC5") (pin "A3") (pinfunction "OUTP_A3") (pintype "passive"))
      (node (ref "IC8") (pin "9") (pinfunction "OUTP_9") (pintype "passive"))
      (node (ref "L4") (pin "1") (pinfunction "1_1") (pintype "passive"))
    )
    (net (code "28") (name "/S~{D}") (class "Default")
      (node (ref "IC5") (pin "A1") (pinfunction "~{SD_MODE}_A1") (pintype "passive"))
      (node (ref "IC8") (pin "4") (pinfunction "~{SD_MODE}_4") (pintype "passive"))
      (node (ref "R17") (pin "2") (pinfunction "2_2") (pintype "passive"))
    )
    (net (code "29") (name "/UART2_RX") (class "Default")
      (node (ref "H1") (pin "12") (pinfunction "12_12") (pintype "passive"))
      (node (ref "U3") (pin "6") (pinfunction "6_6") (pintype "passive"))
    )
    (net (code "30") (name "/UART2_TX") (class "Default")
      (node (ref "H1") (pin "11") (pinfunction "11_11") (pintype "passive"))
      (node (ref "U3") (pin "4") (pinfunction "4_4") (pintype "passive"))
    )
    (net (code "31") (name "/USB_DN") (class "Default")
      (node (ref "U3") (pin "3") (pinfunction "3_3") (pintype "passive"))
    )
    (net (code "32") (name "/USB_DP") (class "Default")
      (node (ref "U3") (pin "5") (pinfunction "5_5") (pintype "passive"))
    )
    (net (code "33") (name "GND") (class "Default")
      (node (ref "C18") (pin "1") (pinfunction "1_1") (pintype "passive"))
      (node (ref "C19") (pin "1") (pinfunction "1_1") (pintype "passive"))
      (node (ref "C22") (pin "1") (pinfunction "1_1") (pintype "passive"))
      (node (ref "C23") (pin "1") (pinfunction "1_1") (pintype "passive"))
      (node (ref "C24") (pin "1") (pinfunction "1_1") (pintype "passive"))
      (node (ref "C25") (pin "1") (pinfunction "1_1") (pintype "passive"))
      (node (ref "C26") (pin "2") (pinfunction "2_2") (pintype "passive"))
      (node (ref "C27") (pin "1") (pinfunction "1_1") (pintype "passive"))
      (node (ref "C38") (pin "1") (pinfunction "1_1") (pintype "passive"))
      (node (ref "C39") (pin "1") (pinfunction "1_1") (pintype "passive"))
      (node (ref "C40") (pin "1") (pinfunction "1_1") (pintype "passive"))
      (node (ref "C40") (pin "2") (pinfunction "2_2") (pintype "passive"))
      (node (ref "C40") (pin "3") (pinfunction "3_3") (pintype "passive"))
      (node (ref "C43") (pin "1") (pinfunction "1_1") (pintype "passive"))
      (node (ref "C43") (pin "2") (pinfunction "2_2") (pintype "passive"))
      (node (ref "C43") (pin "3") (pinfunction "3_3") (pintype "passive"))
      (node (ref "C46") (pin "1") (pinfunction "1_1") (pintype "passive"))
      (node (ref "C46") (pin "2") (pinfunction "2_2") (pintype "passive"))
      (node (ref "C46") (pin "3") (pinfunction "3_3") (pintype "passive"))
      (node (ref "C49") (pin "1") (pinfunction "1_1") (pintype "passive"))
      (node (ref "C49") (pin "2") (pinfunction "2_2") (pintype "passive"))
      (node (ref "C49") (pin "3") (pinfunction "3_3") (pintype "passive"))
      (node (ref "FB2") (pin "1") (pinfunction "1_1") (pintype "passive"))
      (node (ref "H1") (pin "1") (pinfunction "1_1") (pintype "passive"))
      (node (ref "H1") (pin "3") (pinfunction "3_3") (pintype "passive"))
      (node (ref "H1") (pin "5") (pinfunction "5_5") (pintype "passive"))
      (node (ref "H1") (pin "7") (pinfunction "7_7") (pintype "passive"))
      (node (ref "IC3") (pin "14") (pinfunction "VSS_14") (pintype "passive"))
      (node (ref "IC3") (pin "24") (pinfunction "A5_24") (pintype "passive"))
      (node (ref "IC3") (pin "25") (pinfunction "EXTCLK_25") (pintype "passive"))
      (node (ref "IC3") (pin "3") (pinfunction "A2_3") (pintype "passive"))
      (node (ref "IC3") (pin "4") (pinfunction "A3_4") (pintype "passive"))
      (node (ref "IC3") (pin "5") (pinfunction "A4_5") (pintype "passive"))
      (node (ref "IC5") (pin "B2") (pinfunction "GAIN_SLOT_B2") (pintype "passive"))
      (node (ref "IC5") (pin "C2") (pinfunction "GND_C2") (pintype "passive"))
      (node (ref "IC8") (pin "11") (pinfunction "GND_2_11") (pintype "passive"))
      (node (ref "IC8") (pin "15") (pinfunction "GND_3_15") (pintype "passive"))
      (node (ref "IC8") (pin "17") (pinfunction "GND_4_17") (pintype "passive"))
      (node (ref "IC8") (pin "2") (pinfunction "GAIN_SLOT_2") (pintype "passive"))
      (node (ref "IC8") (pin "3") (pinfunction "GND_1_3") (pintype "passive"))
      (node (ref "LED1") (pin "3") (pinfunction "VSS_3") (pintype "passive"))
      (node (ref "LED10") (pin "3") (pinfunction "VSS_3") (pintype "passive"))
      (node (ref "LED11") (pin "3") (pinfunction "VSS_3") (pintype "passive"))
      (node (ref "LED12") (pin "3") (pinfunction "VSS_3") (pintype "passive"))
      (node (ref "LED2") (pin "3") (pinfunction "VSS_3") (pintype "passive"))
      (node (ref "LED3") (pin "3") (pinfunction "VSS_3") (pintype "passive"))
      (node (ref "LED4") (pin "3") (pinfunction "VSS_3") (pintype "passive"))
      (node (ref "LED5") (pin "3") (pinfunction "VSS_3") (pintype "passive"))
      (node (ref "LED6") (pin "3") (pinfunction "VSS_3") (pintype "passive"))
      (node (ref "LED7") (pin "3") (pinfunction "VSS_3") (pintype "passive"))
      (node (ref "LED8") (pin "3") (pinfunction "VSS_3") (pintype "passive"))
      (node (ref "LED9") (pin "3") (pinfunction "VSS_3") (pintype "passive"))
      (node (ref "R27") (pin "1") (pinfunction "1_1") (pintype "passive"))
      (node (ref "R28") (pin "1") (pinfunction "1_1") (pintype "passive"))
      (node (ref "U1") (pin "15") (pinfunction "15_15") (pintype "passive"))
      (node (ref "U1") (pin "16") (pinfunction "16_16") (pintype "passive"))
      (node (ref "U4") (pin "1") (pinfunction "SDO/SA0_1") (pintype "bidirectional"))
      (node (ref "U4") (pin "6") (pinfunction "GND_6") (pintype "power_in"))
      (node (ref "U4") (pin "7") (pinfunction "GND_7") (pintype "power_in"))
    )
    (net (code "34") (name "GND_ISO") (class "Default")
      (node (ref "C29") (pin "1") (pinfunction "1_1") (pintype "passive"))
      (node (ref "C30") (pin "1") (pinfunction "1_1") (pintype "passive"))
      (node (ref "C31") (pin "2") (pinfunction "2_2") (pintype "passive"))
      (node (ref "C32") (pin "1") (pinfunction "1_1") (pintype "passive"))
      (node (ref "FB2") (pin "2") (pinfunction "2_2") (pintype "passive"))
      (node (ref "IC6") (pin "10") (pinfunction "GAIN_10") (pintype "passive"))
      (node (ref "IC6") (pin "15") (pinfunction "EP_15") (pintype "passive"))
      (node (ref "IC6") (pin "7") (pinfunction "GND_7") (pintype "passive"))
      (node (ref "IC6") (pin "9") (pinfunction "A/R_9") (pintype "passive"))
      (node (ref "MIC1") (pin "2") (pinfunction "2_2") (pintype "passive"))
      (node (ref "R30") (pin "2") (pinfunction "2_2") (pintype "passive"))
    )
    (net (code "35") (name "MICBIAS") (class "Default")
      (node (ref "IC6") (pin "13") (pinfunction "MICBIAS_13") (pintype "passive"))
      (node (ref "R31") (pin "1") (pinfunction "1_1") (pintype "passive"))
      (node (ref "R32") (pin "2") (pinfunction "2_2") (pintype "passive"))
    )
    (net (code "36") (name "Net-(C26-Pad1)") (class "Default")
      (node (ref "C26") (pin "1") (pinfunction "1_1") (pintype "passive"))
      (node (ref "L2") (pin "2") (pinfunction "2_2") (pintype "passive"))
      (node (ref "TP1") (pin "1") (pinfunction "1_1") (pintype "passive"))
    )
    (net (code "37") (name "Net-(C27-Pad2)") (class "Default")
      (node (ref "C27") (pin "2") (pinfunction "2_2") (pintype "passive"))
      (node (ref "L4") (pin "2") (pinfunction "2_2") (pintype "passive"))
      (node (ref "TP2") (pin "1") (pinfunction "1_1") (pintype "passive"))
    )
    (net (code "38") (name "Net-(C28-Pad2)") (class "Default")
      (node (ref "C28") (pin "2") (pinfunction "2_2") (pintype "passive"))
      (node (ref "MIC1") (pin "1") (pinfunction "1_1") (pintype "passive"))
      (node (ref "R32") (pin "1") (pinfunction "1_1") (pintype "passive"))
    )
    (net (code "39") (name "Net-(IC3-A0)") (class "Default")
      (node (ref "IC3") (pin "1") (pinfunction "A0_1") (pintype "passive"))
      (node (ref "R12") (pin "1") (pinfunction "1_1") (pintype "passive"))
    )
    (net (code "40") (name "Net-(IC3-A1)") (class "Default")
      (node (ref "IC3") (pin "2") (pinfunction "A1_2") (pintype "passive"))
      (node (ref "R13") (pin "1") (pinfunction "1_1") (pintype "passive"))
    )
    (net (code "41") (name "Net-(IC3-LED0)") (class "Default")
      (node (ref "IC3") (pin "6") (pinfunction "LED0_6") (pintype "passive"))
      (node (ref "R35") (pin "2") (pinfunction "2_2") (pintype "passive"))
    )
    (net (code "42") (name "Net-(IC3-LED1)") (class "Default")
      (node (ref "IC3") (pin "7") (pinfunction "LED1_7") (pintype "passive"))
      (node (ref "R36") (pin "2") (pinfunction "2_2") (pintype "passive"))
    )
    (net (code "43") (name "Net-(IC3-LED2)") (class "Default")
      (node (ref "IC3") (pin "8") (pinfunction "LED2_8") (pintype "passive"))
      (node (ref "R37") (pin "2") (pinfunction "2_2") (pintype "passive"))
    )
    (net (code "44") (name "Net-(IC3-LED3)") (class "Default")
      (node (ref "IC3") (pin "9") (pinfunction "LED3_9") (pintype "passive"))
      (node (ref "R38") (pin "2") (pinfunction "2_2") (pintype "passive"))
    )
    (net (code "45") (name "Net-(IC3-LED4)") (class "Default")
      (node (ref "IC3") (pin "10") (pinfunction "LED4_10") (pintype "passive"))
      (node (ref "R39") (pin "2") (pinfunction "2_2") (pintype "passive"))
    )
    (net (code "46") (name "Net-(IC3-LED5)") (class "Default")
      (node (ref "IC3") (pin "11") (pinfunction "LED5_11") (pintype "passive"))
      (node (ref "R40") (pin "2") (pinfunction "2_2") (pintype "passive"))
    )
    (net (code "47") (name "Net-(IC3-LED6)") (class "Default")
      (node (ref "IC3") (pin "12") (pinfunction "LED6_12") (pintype "passive"))
      (node (ref "R41") (pin "2") (pinfunction "2_2") (pintype "passive"))
    )
    (net (code "48") (name "Net-(IC3-LED7)") (class "Default")
      (node (ref "IC3") (pin "13") (pinfunction "LED7_13") (pintype "passive"))
      (node (ref "R42") (pin "2") (pinfunction "2_2") (pintype "passive"))
    )
    (net (code "49") (name "Net-(IC3-LED8)") (class "Default")
      (node (ref "IC3") (pin "15") (pinfunction "LED8_15") (pintype "passive"))
      (node (ref "R50") (pin "1") (pinfunction "1_1") (pintype "passive"))
    )
    (net (code "50") (name "Net-(IC3-LED9)") (class "Default")
      (node (ref "IC3") (pin "16") (pinfunction "LED9_16") (pintype "passive"))
      (node (ref "R49") (pin "1") (pinfunction "1_1") (pintype "passive"))
    )
    (net (code "51") (name "Net-(IC3-LED10)") (class "Default")
      (node (ref "IC3") (pin "17") (pinfunction "LED10_17") (pintype "passive"))
      (node (ref "R48") (pin "1") (pinfunction "1_1") (pintype "passive"))
    )
    (net (code "52") (name "Net-(IC3-LED11)") (class "Default")
      (node (ref "IC3") (pin "18") (pinfunction "LED11_18") (pintype "passive"))
      (node (ref "R47") (pin "1") (pinfunction "1_1") (pintype "passive"))
    )
    (net (code "53") (name "Net-(IC6-BIAS)") (class "Default")
      (node (ref "C29") (pin "2") (pinfunction "2_2") (pintype "passive"))
      (node (ref "IC6") (pin "12") (pinfunction "BIAS_12") (pintype "passive"))
    )
    (net (code "54") (name "Net-(IC6-CG)") (class "Default")
      (node (ref "C32") (pin "2") (pinfunction "2_2") (pintype "passive"))
      (node (ref "IC6") (pin "3") (pinfunction "CG_3") (pintype "passive"))
    )
    (net (code "55") (name "Net-(IC6-CT)") (class "Default")
      (node (ref "C31") (pin "1") (pinfunction "1_1") (pintype "passive"))
      (node (ref "IC6") (pin "1") (pinfunction "CT_1") (pintype "passive"))
    )
    (net (code "56") (name "Net-(IC6-MICIN)") (class "Default")
      (node (ref "C28") (pin "1") (pinfunction "1_1") (pintype "passive"))
      (node (ref "IC6") (pin "8") (pinfunction "MICIN_8") (pintype "passive"))
    )
    (net (code "57") (name "Net-(IC6-MICOUT)") (class "Default")
      (node (ref "C33") (pin "2") (pinfunction "2_2") (pintype "passive"))
      (node (ref "IC6") (pin "6") (pinfunction "MICOUT_6") (pintype "passive"))
    )
    (net (code "58") (name "Net-(IC6-TH)") (class "Default")
      (node (ref "IC6") (pin "14") (pinfunction "TH_14") (pintype "passive"))
      (node (ref "R30") (pin "1") (pinfunction "1_1") (pintype "passive"))
      (node (ref "R31") (pin "2") (pinfunction "2_2") (pintype "passive"))
    )
    (net (code "59") (name "Net-(IC6-VDD)") (class "Default")
      (node (ref "C30") (pin "2") (pinfunction "2_2") (pintype "passive"))
      (node (ref "FB1") (pin "1") (pinfunction "1_1") (pintype "passive"))
      (node (ref "IC6") (pin "2") (pinfunction "~{SHDN}_2") (pintype "passive"))
      (node (ref "IC6") (pin "5") (pinfunction "VDD_5") (pintype "passive"))
    )
    (net (code "60") (name "Net-(LED1-DOUT)") (class "Default")
      (node (ref "LED1") (pin "2") (pinfunction "DOUT_2") (pintype "passive"))
      (node (ref "LED2") (pin "4") (pinfunction "DIN_4") (pintype "passive"))
    )
    (net (code "61") (name "Net-(LED2-DOUT)") (class "Default")
      (node (ref "LED2") (pin "2") (pinfunction "DOUT_2") (pintype "passive"))
      (node (ref "LED3") (pin "4") (pinfunction "DIN_4") (pintype "passive"))
    )
    (net (code "62") (name "Net-(LED3-DOUT)") (class "Default")
      (node (ref "LED3") (pin "2") (pinfunction "DOUT_2") (pintype "passive"))
      (node (ref "LED4") (pin "4") (pinfunction "DIN_4") (pintype "passive"))
    )
    (net (code "63") (name "Net-(LED4-DOUT)") (class "Default")
      (node (ref "LED4") (pin "2") (pinfunction "DOUT_2") (pintype "passive"))
      (node (ref "LED5") (pin "4") (pinfunction "DIN_4") (pintype "passive"))
    )
    (net (code "64") (name "Net-(LED5-DOUT)") (class "Default")
      (node (ref "LED5") (pin "2") (pinfunction "DOUT_2") (pintype "passive"))
      (node (ref "LED6") (pin "4") (pinfunction "DIN_4") (pintype "passive"))
    )
    (net (code "65") (name "Net-(LED6-DOUT)") (class "Default")
      (node (ref "LED6") (pin "2") (pinfunction "DOUT_2") (pintype "passive"))
      (node (ref "LED7") (pin "4") (pinfunction "DIN_4") (pintype "passive"))
    )
    (net (code "66") (name "Net-(LED7-DOUT)") (class "Default")
      (node (ref "LED7") (pin "2") (pinfunction "DOUT_2") (pintype "passive"))
      (node (ref "LED8") (pin "4") (pinfunction "DIN_4") (pintype "passive"))
    )
    (net (code "67") (name "Net-(LED8-DOUT)") (class "Default")
      (node (ref "LED8") (pin "2") (pinfunction "DOUT_2") (pintype "passive"))
      (node (ref "LED9") (pin "4") (pinfunction "DIN_4") (pintype "passive"))
    )
    (net (code "68") (name "Net-(LED10-DIN)") (class "Default")
      (node (ref "LED10") (pin "4") (pinfunction "DIN_4") (pintype "passive"))
      (node (ref "LED9") (pin "2") (pinfunction "DOUT_2") (pintype "passive"))
    )
    (net (code "69") (name "Net-(LED10-DOUT)") (class "Default")
      (node (ref "LED10") (pin "2") (pinfunction "DOUT_2") (pintype "passive"))
      (node (ref "LED11") (pin "4") (pinfunction "DIN_4") (pintype "passive"))
    )
    (net (code "70") (name "Net-(LED11-DOUT)") (class "Default")
      (node (ref "LED11") (pin "2") (pinfunction "DOUT_2") (pintype "passive"))
      (node (ref "LED12") (pin "4") (pinfunction "DIN_4") (pintype "passive"))
    )
    (net (code "71") (name "VBAT_SW") (class "Default")
      (node (ref "R25") (pin "2") (pinfunction "2_2") (pintype "passive"))
    )
    (net (code "72") (name "VBUS") (class "Default")
      (node (ref "R26") (pin "2") (pinfunction "2_2") (pintype "passive"))
    )
    (net (code "73") (name "unconnected-(IC3-LED12-Pad19)") (class "Default")
      (node (ref "IC3") (pin "19") (pinfunction "LED12_19") (pintype "passive"))
    )
    (net (code "74") (name "unconnected-(IC3-LED13-Pad20)") (class "Default")
      (node (ref "IC3") (pin "20") (pinfunction "LED13_20") (pintype "passive"))
    )
    (net (code "75") (name "unconnected-(IC3-LED14-Pad21)") (class "Default")
      (node (ref "IC3") (pin "21") (pinfunction "LED14_21") (pintype "passive"))
    )
    (net (code "76") (name "unconnected-(IC3-LED15-Pad22)") (class "Default")
      (node (ref "IC3") (pin "22") (pinfunction "LED15_22") (pintype "passive"))
    )
    (net (code "77") (name "unconnected-(IC3-~{OE}-Pad23)") (class "Default")
      (node (ref "IC3") (pin "23") (pinfunction "~{OE}_23") (pintype "passive"))
    )
    (net (code "78") (name "unconnected-(IC6-N.C._1-Pad4)") (class "Default")
      (node (ref "IC6") (pin "4") (pinfunction "N.C._1_4") (pintype "passive+no_connect"))
    )
    (net (code "79") (name "unconnected-(IC6-N.C._2-Pad11)") (class "Default")
      (node (ref "IC6") (pin "11") (pinfunction "N.C._2_11") (pintype "passive+no_connect"))
    )
    (net (code "80") (name "unconnected-(IC8-N.C._1-Pad5)") (class "Default")
      (node (ref "IC8") (pin "5") (pinfunction "N.C._1_5") (pintype "passive+no_connect"))
    )
    (net (code "81") (name "unconnected-(IC8-N.C._2-Pad6)") (class "Default")
      (node (ref "IC8") (pin "6") (pinfunction "N.C._2_6") (pintype "passive+no_connect"))
    )
    (net (code "82") (name "unconnected-(IC8-N.C._3-Pad12)") (class "Default")
      (node (ref "IC8") (pin "12") (pinfunction "N.C._3_12") (pintype "passive+no_connect"))
    )
    (net (code "83") (name "unconnected-(IC8-N.C._4-Pad13)") (class "Default")
      (node (ref "IC8") (pin "13") (pinfunction "N.C._4_13") (pintype "passive+no_connect"))
    )
    (net (code "84") (name "unconnected-(LED12-DOUT-Pad2)") (class "Default")
      (node (ref "LED12") (pin "2") (pinfunction "DOUT_2") (pintype "passive+no_connect"))
    )
    (net (code "85") (name "unconnected-(U1-Pad4)") (class "Default")
      (node (ref "U1") (pin "4") (pinfunction "4_4") (pintype "passive"))
    )
    (net (code "86") (name "unconnected-(U2-Pad1)") (class "Default")
      (node (ref "U2") (pin "1") (pinfunction "1_1") (pintype "passive"))
    )
    (net (code "87") (name "unconnected-(U2-Pad2)") (class "Default")
      (node (ref "U2") (pin "2") (pinfunction "2_2") (pintype "passive"))
    )
    (net (code "88") (name "unconnected-(U2-Pad3)") (class "Default")
      (node (ref "U2") (pin "3") (pinfunction "3_3") (pintype "passive"))
    )
    (net (code "89") (name "unconnected-(U2-Pad4)") (class "Default")
      (node (ref "U2") (pin "4") (pinfunction "4_4") (pintype "passive"))
    )
    (net (code "90") (name "unconnected-(U2-Pad5)") (class "Default")
      (node (ref "U2") (pin "5") (pinfunction "5_5") (pintype "passive"))
    )
    (net (code "91") (name "unconnected-(U2-Pad6)") (class "Default")
      (node (ref "U2") (pin "6") (pinfunction "6_6") (pintype "passive"))
    )
    (net (code "92") (name "unconnected-(U4-INT1-Pad4)") (class "Default")
      (node (ref "U4") (pin "4") (pinfunction "INT1_4") (pintype "output"))
    )
    (net (code "93") (name "unconnected-(U4-INT2-Pad9)") (class "Default")
      (node (ref "U4") (pin "9") (pinfunction "INT2_9") (pintype "output"))
    )
    (net (code "94") (name "unconnected-(U4-SCX-Pad3)") (class "Default")
      (node (ref "U4") (pin "3") (pinfunction "SCX_3") (pintype "bidirectional"))
    )
    (net (code "95") (name "unconnected-(U4-SDX-Pad2)") (class "Default")
      (node (ref "U4") (pin "2") (pinfunction "SDX_2") (pintype "bidirectional"))
    )
  )
)
